# MCU.net
KiCad netlist of a schematic drawn in Altium Designer
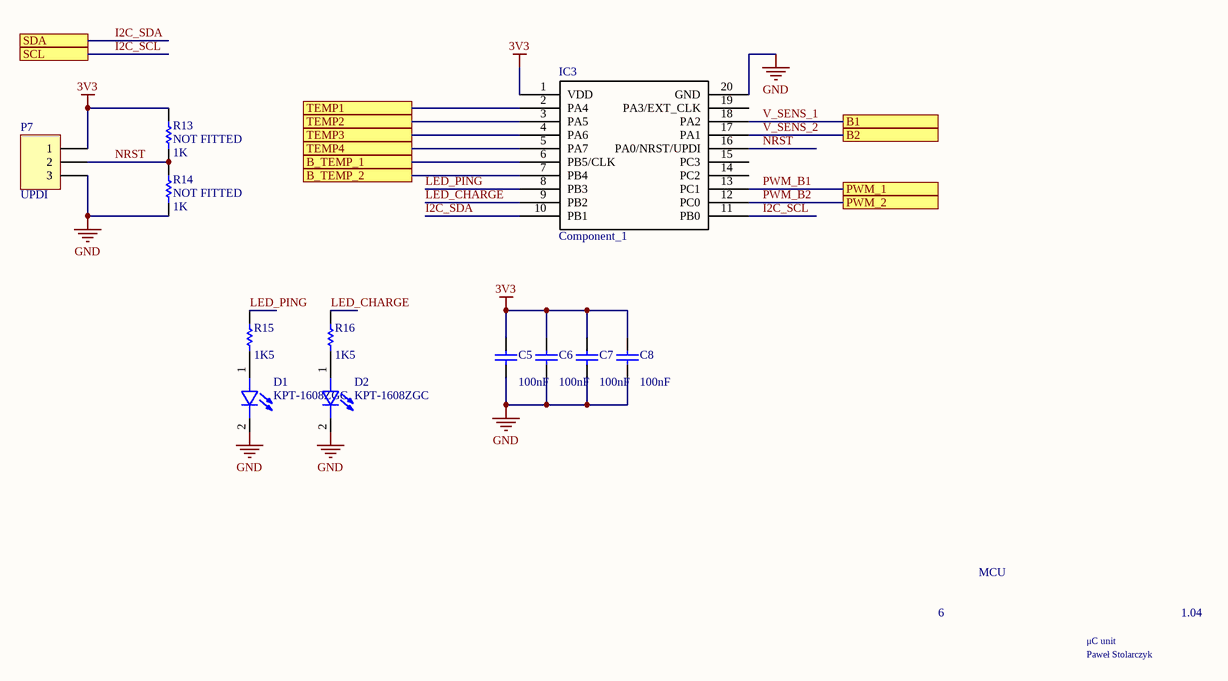
[diagram p0: MCU.SchDoc]

(export (version "E")
  (design (tool "Eeschema 10.0.6"))
  (components
    (comp (ref "C5")
      (value "100nF")
      (footprint "0402")
      (description "Capacitor")
      (fields (field (name "Comment") "Cap") (field (name "PUBLISHER") "Altium Limited"))
      (libsource (lib "Miscellaneous Devices") (part "Cap"))
    )
    (comp (ref "C6")
      (value "100nF")
      (footprint "0402")
      (description "Capacitor")
      (fields (field (name "Comment") "Cap") (field (name "PUBLISHER") "Altium Limited"))
      (libsource (lib "Miscellaneous Devices") (part "Cap"))
    )
    (comp (ref "C7")
      (value "100nF")
      (footprint "0402")
      (description "Capacitor")
      (fields (field (name "Comment") "Cap") (field (name "PUBLISHER") "Altium Limited"))
      (libsource (lib "Miscellaneous Devices") (part "Cap"))
    )
    (comp (ref "C8")
      (value "100nF")
      (footprint "0402")
      (description "Capacitor")
      (fields (field (name "Comment") "Cap") (field (name "PUBLISHER") "Altium Limited"))
      (libsource (lib "Miscellaneous Devices") (part "Cap"))
    )
    (comp (ref "D1")
      (value "KPT-1608ZGC")
      (footprint "LED_KPT-1608ZGC")
      (description "1.6x0.8mm Smd Chip Led Lamp")
      (fields (field (name "MF") "Kingbright"))
      (libsource (lib "KPT-1608ZGC") (part "KPT-1608ZGC"))
    )
    (comp (ref "D2")
      (value "KPT-1608ZGC")
      (footprint "LED_KPT-1608ZGC")
      (description "1.6x0.8mm Smd Chip Led Lamp")
      (fields (field (name "MF") "Kingbright"))
      (libsource (lib "KPT-1608ZGC") (part "KPT-1608ZGC"))
    )
    (comp (ref "IC3")
      (value "Component_1")
      (footprint "SOIC127P1032X265-20N")
      (libsource (lib "Attiny806") (part "Component_1"))
    )
    (comp (ref "P7")
      (value "UPDI")
      (footprint "HDR1X3")
      (description "Header, 3-Pin")
      (fields (field (name "PUBLISHER") "Altium Limited"))
      (libsource (lib "Miscellaneous Connectors") (part "Header 3"))
    )
    (comp (ref "R13")
      (value "NOT FITTED")
      (footprint "0402")
      (description "Resistor")
      (fields (field (name "ALTIUM_VALUE") "1K") (field (name "PUBLISHER") "Altium Limited"))
      (libsource (lib "Miscellaneous Devices") (part "Res1"))
    )
    (comp (ref "R14")
      (value "NOT FITTED")
      (footprint "0402")
      (description "Resistor")
      (fields (field (name "ALTIUM_VALUE") "1K") (field (name "PUBLISHER") "Altium Limited"))
      (libsource (lib "Miscellaneous Devices") (part "Res1"))
    )
    (comp (ref "R15")
      (value "1K5")
      (footprint "0402")
      (description "Resistor")
      (fields (field (name "Comment") "NOT FITTED") (field (name "PUBLISHER") "Altium Limited"))
      (libsource (lib "Miscellaneous Devices") (part "Res1"))
    )
    (comp (ref "R16")
      (value "1K5")
      (footprint "0402")
      (description "Resistor")
      (fields (field (name "Comment") "NOT FITTED") (field (name "PUBLISHER") "Altium Limited"))
      (libsource (lib "Miscellaneous Devices") (part "Res1"))
    )
  )
  (nets
    (net (code "1") (name "/B_TEMP_1") (class "Default")
      (node (ref "IC3") (pin "6") (pinfunction "PB5/CLK_6") (pintype "passive"))
    )
    (net (code "2") (name "/B_TEMP_2") (class "Default")
      (node (ref "IC3") (pin "7") (pinfunction "PB4_7") (pintype "passive"))
    )
    (net (code "3") (name "/I2C_SCL") (class "Default")
      (node (ref "IC3") (pin "11") (pinfunction "PB0_11") (pintype "passive"))
    )
    (net (code "4") (name "/I2C_SDA") (class "Default")
      (node (ref "IC3") (pin "10") (pinfunction "PB1_10") (pintype "passive"))
    )
    (net (code "5") (name "/LED_CHARGE") (class "Default")
      (node (ref "IC3") (pin "9") (pinfunction "PB2_9") (pintype "passive"))
      (node (ref "R16") (pin "1") (pinfunction "1_1") (pintype "passive"))
    )
    (net (code "6") (name "/LED_PING") (class "Default")
      (node (ref "IC3") (pin "8") (pinfunction "PB3_8") (pintype "passive"))
      (node (ref "R15") (pin "1") (pinfunction "1_1") (pintype "passive"))
    )
    (net (code "7") (name "/NRST") (class "Default")
      (node (ref "IC3") (pin "16") (pinfunction "PA0/NRST/UPDI_16") (pintype "passive"))
      (node (ref "P7") (pin "2") (pinfunction "2_2") (pintype "passive"))
      (node (ref "R13") (pin "2") (pinfunction "2_2") (pintype "passive"))
      (node (ref "R14") (pin "1") (pinfunction "1_1") (pintype "passive"))
    )
    (net (code "8") (name "/PWM_B1") (class "Default")
      (node (ref "IC3") (pin "13") (pinfunction "PC1_13") (pintype "passive"))
    )
    (net (code "9") (name "/PWM_B2") (class "Default")
      (node (ref "IC3") (pin "12") (pinfunction "PC0_12") (pintype "passive"))
    )
    (net (code "10") (name "/TEMP1") (class "Default")
      (node (ref "IC3") (pin "2") (pinfunction "PA4_2") (pintype "passive"))
    )
    (net (code "11") (name "/TEMP2") (class "Default")
      (node (ref "IC3") (pin "3") (pinfunction "PA5_3") (pintype "passive"))
    )
    (net (code "12") (name "/TEMP3") (class "Default")
      (node (ref "IC3") (pin "4") (pinfunction "PA6_4") (pintype "passive"))
    )
    (net (code "13") (name "/TEMP4") (class "Default")
      (node (ref "IC3") (pin "5") (pinfunction "PA7_5") (pintype "passive"))
    )
    (net (code "14") (name "/V_SENS_1") (class "Default")
      (node (ref "IC3") (pin "18") (pinfunction "PA2_18") (pintype "passive"))
    )
    (net (code "15") (name "/V_SENS_2") (class "Default")
      (node (ref "IC3") (pin "17") (pinfunction "PA1_17") (pintype "passive"))
    )
    (net (code "16") (name "3V3") (class "Default")
      (node (ref "C5") (pin "2") (pinfunction "2_2") (pintype "passive"))
      (node (ref "C6") (pin "2") (pinfunction "2_2") (pintype "passive"))
      (node (ref "C7") (pin "2") (pinfunction "2_2") (pintype "passive"))
      (node (ref "C8") (pin "2") (pinfunction "2_2") (pintype "passive"))
      (node (ref "IC3") (pin "1") (pinfunction "VDD_1") (pintype "passive"))
      (node (ref "P7") (pin "1") (pinfunction "1_1") (pintype "passive"))
      (node (ref "R13") (pin "1") (pinfunction "1_1") (pintype "passive"))
    )
    (net (code "17") (name "GND") (class "Default")
      (node (ref "C5") (pin "1") (pinfunction "1_1") (pintype "passive"))
      (node (ref "C6") (pin "1") (pinfunction "1_1") (pintype "passive"))
      (node (ref "C7") (pin "1") (pinfunction "1_1") (pintype "passive"))
      (node (ref "C8") (pin "1") (pinfunction "1_1") (pintype "passive"))
      (node (ref "D1") (pin "2") (pinfunction "C_2") (pintype "passive"))
      (node (ref "D2") (pin "2") (pinfunction "C_2") (pintype "passive"))
      (node (ref "IC3") (pin "20") (pinfunction "GND_20") (pintype "passive"))
      (node (ref "P7") (pin "3") (pinfunction "3_3") (pintype "passive"))
      (node (ref "R14") (pin "2") (pinfunction "2_2") (pintype "passive"))
    )
    (net (code "18") (name "Net-(D1-A)") (class "Default")
      (node (ref "D1") (pin "1") (pinfunction "A_1") (pintype "passive"))
      (node (ref "R15") (pin "2") (pinfunction "2_2") (pintype "passive"))
    )
    (net (code "19") (name "Net-(D2-A)") (class "Default")
      (node (ref "D2") (pin "1") (pinfunction "A_1") (pintype "passive"))
      (node (ref "R16") (pin "2") (pinfunction "2_2") (pintype "passive"))
    )
    (net (code "20") (name "unconnected-(IC3-PA3{slash}EXT_CLK-Pad19)") (class "Default")
      (node (ref "IC3") (pin "19") (pinfunction "PA3/EXT_CLK_19") (pintype "passive"))
    )
    (net (code "21") (name "unconnected-(IC3-PC2-Pad14)") (class "Default")
      (node (ref "IC3") (pin "14") (pinfunction "PC2_14") (pintype "passive"))
    )
    (net (code "22") (name "unconnected-(IC3-PC3-Pad15)") (class "Default")
      (node (ref "IC3") (pin "15") (pinfunction "PC3_15") (pintype "passive"))
    )
  )
)
